# Gate_driver.net
KiCad netlist of a schematic drawn in Altium Designer
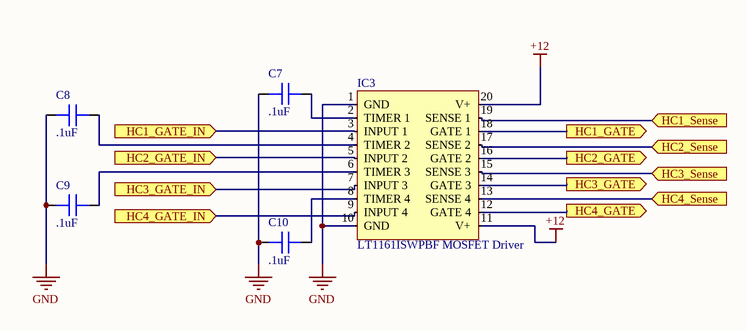
[diagram p0: Gate_driver.SchDoc]

(export (version "E")
  (design (tool "Eeschema 10.0.6"))
  (components
    (comp (ref "C7")
      (value "capacitor")
      (footprint "0603")
      (description "Generic 0603 capacitor")
      (fields (field (name "CAPACITANCE") ".1uF") (field (name "VOLTAGE") "50"))
      (libsource (lib "altlib") (part "capacitor"))
    )
    (comp (ref "C8")
      (value "capacitor")
      (footprint "0603")
      (description "Generic 0603 capacitor")
      (fields (field (name "CAPACITANCE") ".1uF") (field (name "VOLTAGE") "50"))
      (libsource (lib "altlib") (part "capacitor"))
    )
    (comp (ref "C9")
      (value "capacitor")
      (footprint "0603")
      (description "Generic 0603 capacitor")
      (fields (field (name "CAPACITANCE") ".1uF") (field (name "VOLTAGE") "50"))
      (libsource (lib "altlib") (part "capacitor"))
    )
    (comp (ref "C10")
      (value "capacitor")
      (footprint "0603")
      (description "Generic 0603 capacitor")
      (fields (field (name "CAPACITANCE") ".1uF") (field (name "VOLTAGE") "50"))
      (libsource (lib "altlib") (part "capacitor"))
    )
    (comp (ref "IC3")
      (value "LT1161ISWPBF MOSFET Driver")
      (footprint "SO-20")
      (fields (field (name "CREATED_BY") "Eunice Bernardo"))
      (libsource (lib "Altium-Lib") (part "LT1161ISWPBF MOSFET Driver"))
    )
  )
  (nets
    (net (code "1") (name "+12") (class "Default")
      (node (ref "IC3") (pin "11") (pinfunction "V+_11") (pintype "input"))
      (node (ref "IC3") (pin "20") (pinfunction "V+_20") (pintype "input"))
    )
    (net (code "2") (name "/HC1_GATE") (class "Default")
      (node (ref "IC3") (pin "18") (pinfunction "GATE_1_18") (pintype "input"))
    )
    (net (code "3") (name "/HC1_GATE_IN") (class "Default")
      (node (ref "IC3") (pin "3") (pinfunction "INPUT_1_3") (pintype "input"))
    )
    (net (code "4") (name "/HC1_Sense") (class "Default")
      (node (ref "IC3") (pin "19") (pinfunction "SENSE_1_19") (pintype "input"))
    )
    (net (code "5") (name "/HC2_GATE") (class "Default")
      (node (ref "IC3") (pin "16") (pinfunction "GATE_2_16") (pintype "input"))
    )
    (net (code "6") (name "/HC2_GATE_IN") (class "Default")
      (node (ref "IC3") (pin "5") (pinfunction "INPUT_2_5") (pintype "input"))
    )
    (net (code "7") (name "/HC2_Sense") (class "Default")
      (node (ref "IC3") (pin "17") (pinfunction "SENSE_2_17") (pintype "input"))
    )
    (net (code "8") (name "/HC3_GATE") (class "Default")
      (node (ref "IC3") (pin "14") (pinfunction "GATE_3_14") (pintype "input"))
    )
    (net (code "9") (name "/HC3_GATE_IN") (class "Default")
      (node (ref "IC3") (pin "7") (pinfunction "INPUT_3_7") (pintype "input"))
    )
    (net (code "10") (name "/HC3_Sense") (class "Default")
      (node (ref "IC3") (pin "15") (pinfunction "SENSE_3_15") (pintype "input"))
    )
    (net (code "11") (name "/HC4_GATE") (class "Default")
      (node (ref "IC3") (pin "12") (pinfunction "GATE_4_12") (pintype "input"))
    )
    (net (code "12") (name "/HC4_GATE_IN") (class "Default")
      (node (ref "IC3") (pin "9") (pinfunction "INPUT_4_9") (pintype "input"))
    )
    (net (code "13") (name "/HC4_Sense") (class "Default")
      (node (ref "IC3") (pin "13") (pinfunction "SENSE_4_13") (pintype "input"))
    )
    (net (code "14") (name "GND") (class "Default")
      (node (ref "C10") (pin "1") (pinfunction "1_1") (pintype "passive"))
      (node (ref "C7") (pin "1") (pinfunction "1_1") (pintype "passive"))
      (node (ref "C8") (pin "1") (pinfunction "1_1") (pintype "passive"))
      (node (ref "C9") (pin "1") (pinfunction "1_1") (pintype "passive"))
      (node (ref "IC3") (pin "1") (pinfunction "GND_1") (pintype "input"))
      (node (ref "IC3") (pin "10") (pinfunction "GND_10") (pintype "input"))
    )
    (net (code "15") (name "Net-(IC3-TIMER_1)") (class "Default")
      (node (ref "C7") (pin "2") (pinfunction "2_2") (pintype "passive"))
      (node (ref "IC3") (pin "2") (pinfunction "TIMER_1_2") (pintype "input"))
    )
    (net (code "16") (name "Net-(IC3-TIMER_2)") (class "Default")
      (node (ref "C8") (pin "2") (pinfunction "2_2") (pintype "passive"))
      (node (ref "IC3") (pin "4") (pinfunction "TIMER_2_4") (pintype "input"))
    )
    (net (code "17") (name "Net-(IC3-TIMER_3)") (class "Default")
      (node (ref "C9") (pin "2") (pinfunction "2_2") (pintype "passive"))
      (node (ref "IC3") (pin "6") (pinfunction "TIMER_3_6") (pintype "input"))
    )
    (net (code "18") (name "Net-(IC3-TIMER_4)") (class "Default")
      (node (ref "C10") (pin "2") (pinfunction "2_2") (pintype "passive"))
      (node (ref "IC3") (pin "8") (pinfunction "TIMER_4_8") (pintype "input"))
    )
  )
)
